# Solar_LEDs.net
KiCad netlist of a schematic drawn in EAGLE
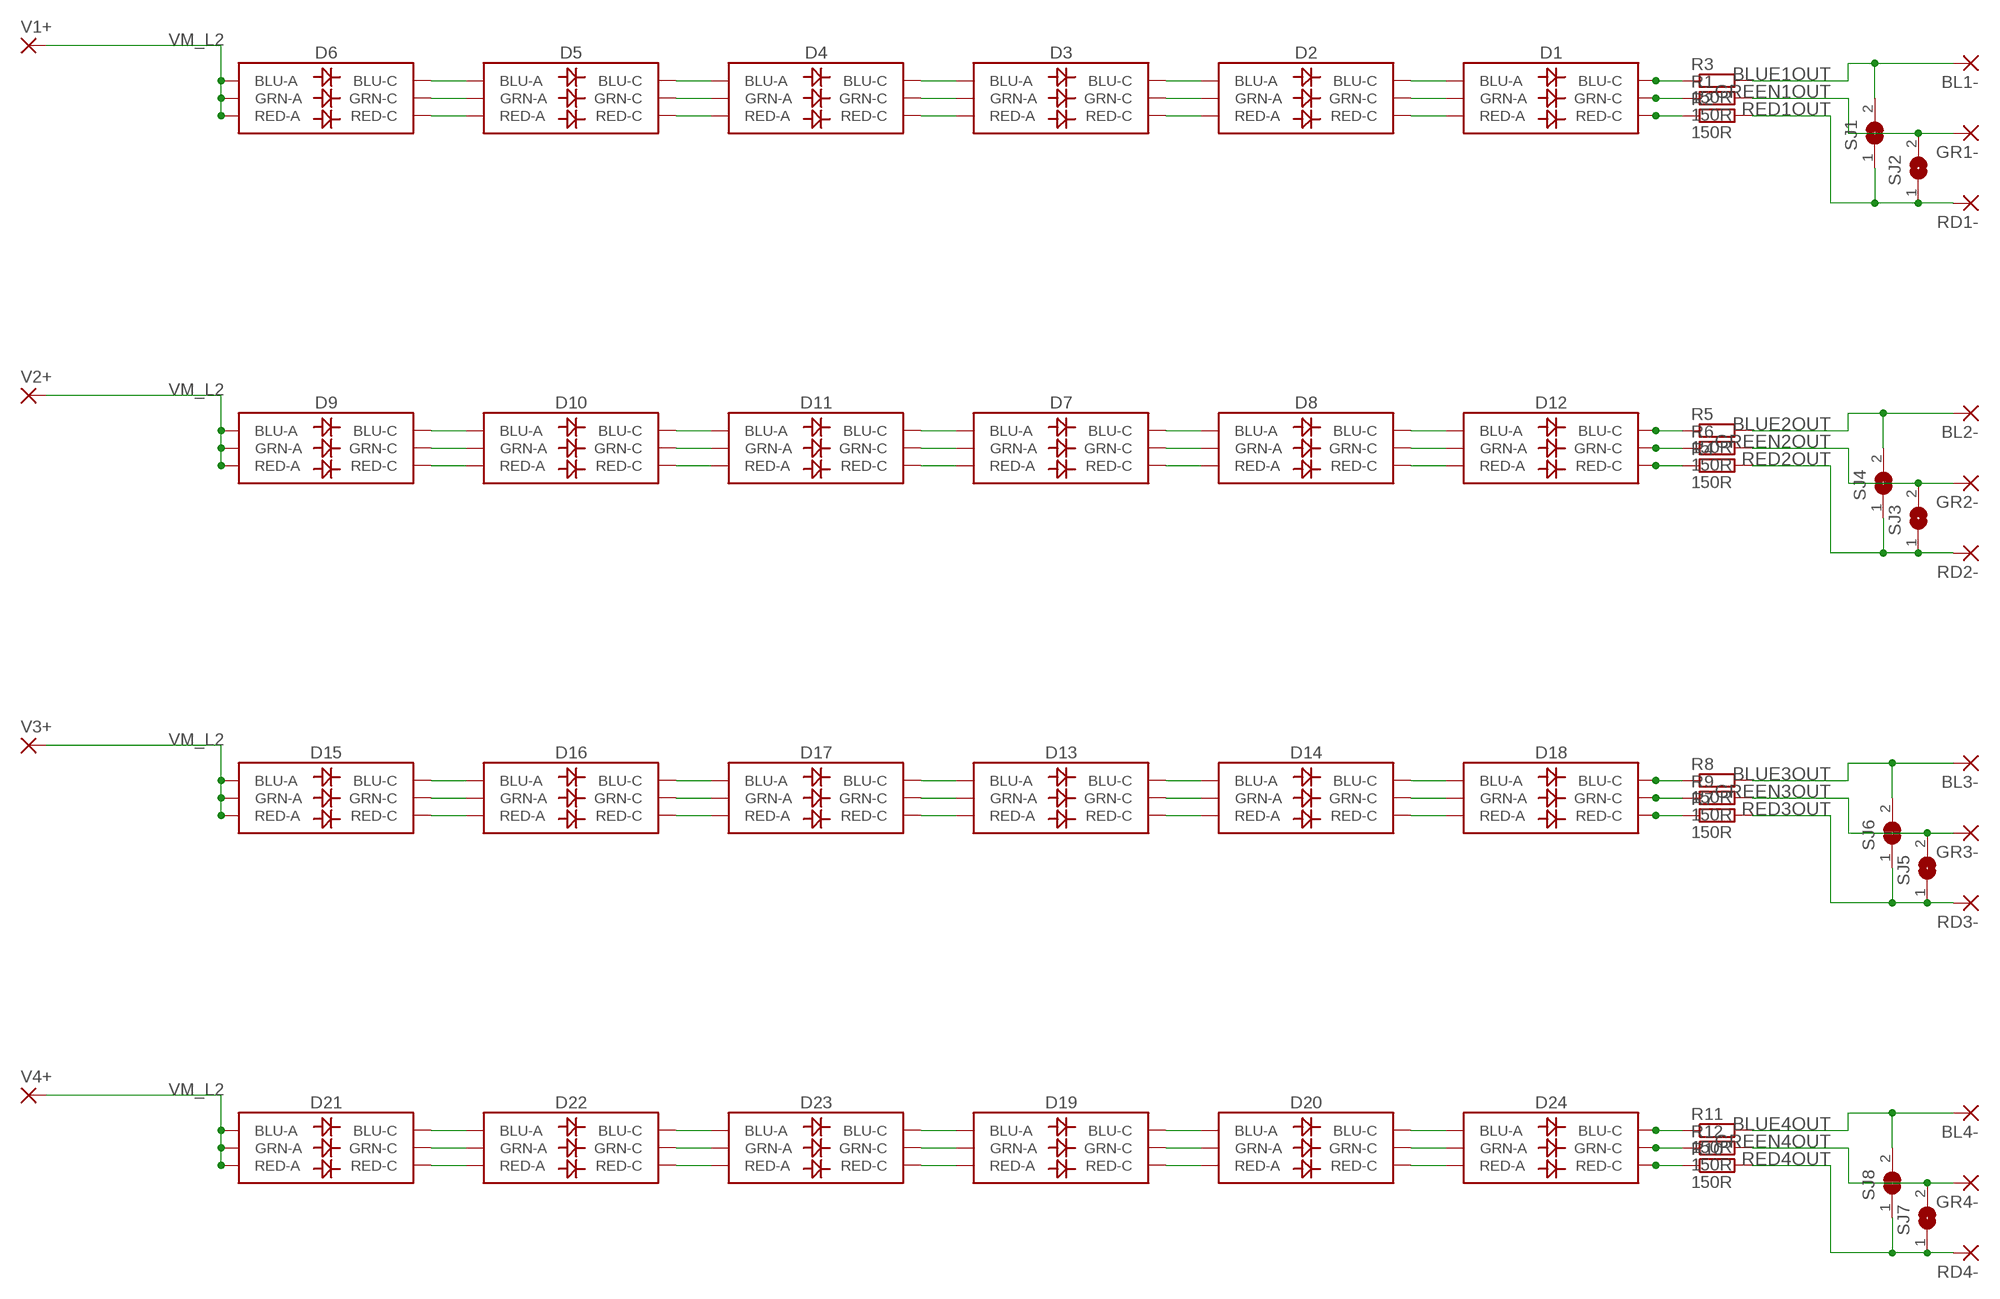
[diagram p0: schematic, sheet 1]

(export (version "E")
  (design (tool "Eeschema 10.0.6"))
  (components
    (comp (ref "BL1-")
      (value "2,54/1,0")
      (footprint "eagle-import:2,54_1,0")
      (libsource (lib "eagle-import") (part "2,54/1,0"))
    )
    (comp (ref "BL2-")
      (value "2,54/1,0")
      (footprint "eagle-import:2,54_1,0")
      (libsource (lib "eagle-import") (part "2,54/1,0"))
    )
    (comp (ref "BL3-")
      (value "2,54/1,0")
      (footprint "eagle-import:2,54_1,0")
      (libsource (lib "eagle-import") (part "2,54/1,0"))
    )
    (comp (ref "BL4-")
      (value "2,54/1,0")
      (footprint "eagle-import:2,54_1,0")
      (libsource (lib "eagle-import") (part "2,54/1,0"))
    )
    (comp (ref "D1")
      (value "LED-RGBNO_IC")
      (footprint "eagle-import:LED-TRICOLOR-5050")
      (libsource (lib "eagle-import") (part "LED-RGBNO_IC"))
    )
    (comp (ref "D2")
      (value "LED-RGBNO_IC")
      (footprint "eagle-import:LED-TRICOLOR-5050")
      (libsource (lib "eagle-import") (part "LED-RGBNO_IC"))
    )
    (comp (ref "D3")
      (value "LED-RGBNO_IC")
      (footprint "eagle-import:LED-TRICOLOR-5050")
      (libsource (lib "eagle-import") (part "LED-RGBNO_IC"))
    )
    (comp (ref "D4")
      (value "LED-RGBNO_IC")
      (footprint "eagle-import:LED-TRICOLOR-5050")
      (libsource (lib "eagle-import") (part "LED-RGBNO_IC"))
    )
    (comp (ref "D5")
      (value "LED-RGBNO_IC")
      (footprint "eagle-import:LED-TRICOLOR-5050")
      (libsource (lib "eagle-import") (part "LED-RGBNO_IC"))
    )
    (comp (ref "D6")
      (value "LED-RGBNO_IC")
      (footprint "eagle-import:LED-TRICOLOR-5050")
      (libsource (lib "eagle-import") (part "LED-RGBNO_IC"))
    )
    (comp (ref "D7")
      (value "LED-RGBNO_IC")
      (footprint "eagle-import:LED-TRICOLOR-5050")
      (libsource (lib "eagle-import") (part "LED-RGBNO_IC"))
    )
    (comp (ref "D8")
      (value "LED-RGBNO_IC")
      (footprint "eagle-import:LED-TRICOLOR-5050")
      (libsource (lib "eagle-import") (part "LED-RGBNO_IC"))
    )
    (comp (ref "D9")
      (value "LED-RGBNO_IC")
      (footprint "eagle-import:LED-TRICOLOR-5050")
      (libsource (lib "eagle-import") (part "LED-RGBNO_IC"))
    )
    (comp (ref "D10")
      (value "LED-RGBNO_IC")
      (footprint "eagle-import:LED-TRICOLOR-5050")
      (libsource (lib "eagle-import") (part "LED-RGBNO_IC"))
    )
    (comp (ref "D11")
      (value "LED-RGBNO_IC")
      (footprint "eagle-import:LED-TRICOLOR-5050")
      (libsource (lib "eagle-import") (part "LED-RGBNO_IC"))
    )
    (comp (ref "D12")
      (value "LED-RGBNO_IC")
      (footprint "eagle-import:LED-TRICOLOR-5050")
      (libsource (lib "eagle-import") (part "LED-RGBNO_IC"))
    )
    (comp (ref "D13")
      (value "LED-RGBNO_IC")
      (footprint "eagle-import:LED-TRICOLOR-5050")
      (libsource (lib "eagle-import") (part "LED-RGBNO_IC"))
    )
    (comp (ref "D14")
      (value "LED-RGBNO_IC")
      (footprint "eagle-import:LED-TRICOLOR-5050")
      (libsource (lib "eagle-import") (part "LED-RGBNO_IC"))
    )
    (comp (ref "D15")
      (value "LED-RGBNO_IC")
      (footprint "eagle-import:LED-TRICOLOR-5050")
      (libsource (lib "eagle-import") (part "LED-RGBNO_IC"))
    )
    (comp (ref "D16")
      (value "LED-RGBNO_IC")
      (footprint "eagle-import:LED-TRICOLOR-5050")
      (libsource (lib "eagle-import") (part "LED-RGBNO_IC"))
    )
    (comp (ref "D17")
      (value "LED-RGBNO_IC")
      (footprint "eagle-import:LED-TRICOLOR-5050")
      (libsource (lib "eagle-import") (part "LED-RGBNO_IC"))
    )
    (comp (ref "D18")
      (value "LED-RGBNO_IC")
      (footprint "eagle-import:LED-TRICOLOR-5050")
      (libsource (lib "eagle-import") (part "LED-RGBNO_IC"))
    )
    (comp (ref "D19")
      (value "LED-RGBNO_IC")
      (footprint "eagle-import:LED-TRICOLOR-5050")
      (libsource (lib "eagle-import") (part "LED-RGBNO_IC"))
    )
    (comp (ref "D20")
      (value "LED-RGBNO_IC")
      (footprint "eagle-import:LED-TRICOLOR-5050")
      (libsource (lib "eagle-import") (part "LED-RGBNO_IC"))
    )
    (comp (ref "D21")
      (value "LED-RGBNO_IC")
      (footprint "eagle-import:LED-TRICOLOR-5050")
      (libsource (lib "eagle-import") (part "LED-RGBNO_IC"))
    )
    (comp (ref "D22")
      (value "LED-RGBNO_IC")
      (footprint "eagle-import:LED-TRICOLOR-5050")
      (libsource (lib "eagle-import") (part "LED-RGBNO_IC"))
    )
    (comp (ref "D23")
      (value "LED-RGBNO_IC")
      (footprint "eagle-import:LED-TRICOLOR-5050")
      (libsource (lib "eagle-import") (part "LED-RGBNO_IC"))
    )
    (comp (ref "D24")
      (value "LED-RGBNO_IC")
      (footprint "eagle-import:LED-TRICOLOR-5050")
      (libsource (lib "eagle-import") (part "LED-RGBNO_IC"))
    )
    (comp (ref "GR1-")
      (value "2,54/1,0")
      (footprint "eagle-import:2,54_1,0")
      (libsource (lib "eagle-import") (part "2,54/1,0"))
    )
    (comp (ref "GR2-")
      (value "2,54/1,0")
      (footprint "eagle-import:2,54_1,0")
      (libsource (lib "eagle-import") (part "2,54/1,0"))
    )
    (comp (ref "GR3-")
      (value "2,54/1,0")
      (footprint "eagle-import:2,54_1,0")
      (libsource (lib "eagle-import") (part "2,54/1,0"))
    )
    (comp (ref "GR4-")
      (value "2,54/1,0")
      (footprint "eagle-import:2,54_1,0")
      (libsource (lib "eagle-import") (part "2,54/1,0"))
    )
    (comp (ref "R1")
      (value "150R")
      (footprint "eagle-import:M1206")
      (libsource (lib "eagle-import") (part "R-EU_M1206"))
    )
    (comp (ref "R2")
      (value "150R")
      (footprint "eagle-import:M1206")
      (libsource (lib "eagle-import") (part "R-EU_M1206"))
    )
    (comp (ref "R3")
      (value "150R")
      (footprint "eagle-import:M1206")
      (libsource (lib "eagle-import") (part "R-EU_M1206"))
    )
    (comp (ref "R4")
      (value "150R")
      (footprint "eagle-import:M1206")
      (libsource (lib "eagle-import") (part "R-EU_M1206"))
    )
    (comp (ref "R5")
      (value "150R")
      (footprint "eagle-import:M1206")
      (libsource (lib "eagle-import") (part "R-EU_M1206"))
    )
    (comp (ref "R6")
      (value "150R")
      (footprint "eagle-import:M1206")
      (libsource (lib "eagle-import") (part "R-EU_M1206"))
    )
    (comp (ref "R7")
      (value "150R")
      (footprint "eagle-import:M1206")
      (libsource (lib "eagle-import") (part "R-EU_M1206"))
    )
    (comp (ref "R8")
      (value "150R")
      (footprint "eagle-import:M1206")
      (libsource (lib "eagle-import") (part "R-EU_M1206"))
    )
    (comp (ref "R9")
      (value "150R")
      (footprint "eagle-import:M1206")
      (libsource (lib "eagle-import") (part "R-EU_M1206"))
    )
    (comp (ref "R10")
      (value "150R")
      (footprint "eagle-import:M1206")
      (libsource (lib "eagle-import") (part "R-EU_M1206"))
    )
    (comp (ref "R11")
      (value "150R")
      (footprint "eagle-import:M1206")
      (libsource (lib "eagle-import") (part "R-EU_M1206"))
    )
    (comp (ref "R12")
      (value "150R")
      (footprint "eagle-import:M1206")
      (libsource (lib "eagle-import") (part "R-EU_M1206"))
    )
    (comp (ref "RD1-")
      (value "2,54/1,0")
      (footprint "eagle-import:2,54_1,0")
      (libsource (lib "eagle-import") (part "2,54/1,0"))
    )
    (comp (ref "RD2-")
      (value "2,54/1,0")
      (footprint "eagle-import:2,54_1,0")
      (libsource (lib "eagle-import") (part "2,54/1,0"))
    )
    (comp (ref "RD3-")
      (value "2,54/1,0")
      (footprint "eagle-import:2,54_1,0")
      (libsource (lib "eagle-import") (part "2,54/1,0"))
    )
    (comp (ref "RD4-")
      (value "2,54/1,0")
      (footprint "eagle-import:2,54_1,0")
      (libsource (lib "eagle-import") (part "2,54/1,0"))
    )
    (comp (ref "SJ1") (value "SJ") (footprint "eagle-import:SJ") (libsource (lib "eagle-import") (part "SJ")))
    (comp (ref "SJ2") (value "SJ") (footprint "eagle-import:SJ") (libsource (lib "eagle-import") (part "SJ")))
    (comp (ref "SJ3") (value "SJ") (footprint "eagle-import:SJ") (libsource (lib "eagle-import") (part "SJ")))
    (comp (ref "SJ4") (value "SJ") (footprint "eagle-import:SJ") (libsource (lib "eagle-import") (part "SJ")))
    (comp (ref "SJ5") (value "SJ") (footprint "eagle-import:SJ") (libsource (lib "eagle-import") (part "SJ")))
    (comp (ref "SJ6") (value "SJ") (footprint "eagle-import:SJ") (libsource (lib "eagle-import") (part "SJ")))
    (comp (ref "SJ7") (value "SJ") (footprint "eagle-import:SJ") (libsource (lib "eagle-import") (part "SJ")))
    (comp (ref "SJ8") (value "SJ") (footprint "eagle-import:SJ") (libsource (lib "eagle-import") (part "SJ")))
    (comp (ref "V1+")
      (value "2,54/1,0")
      (footprint "eagle-import:2,54_1,0")
      (libsource (lib "eagle-import") (part "2,54/1,0"))
    )
    (comp (ref "V2+")
      (value "2,54/1,0")
      (footprint "eagle-import:2,54_1,0")
      (libsource (lib "eagle-import") (part "2,54/1,0"))
    )
    (comp (ref "V3+")
      (value "2,54/1,0")
      (footprint "eagle-import:2,54_1,0")
      (libsource (lib "eagle-import") (part "2,54/1,0"))
    )
    (comp (ref "V4+")
      (value "2,54/1,0")
      (footprint "eagle-import:2,54_1,0")
      (libsource (lib "eagle-import") (part "2,54/1,0"))
    )
  )
  (nets
    (net (code "1") (name "/BLUE1OUT") (class "Default")
      (node (ref "BL1-") (pin "1") (pinfunction "P_1") (pintype "passive"))
      (node (ref "R3") (pin "2") (pinfunction "2_2") (pintype "passive"))
      (node (ref "SJ1") (pin "2") (pinfunction "2_2") (pintype "passive"))
    )
    (net (code "2") (name "/BLUE2OUT") (class "Default")
      (node (ref "BL2-") (pin "1") (pinfunction "P_1") (pintype "passive"))
      (node (ref "R5") (pin "2") (pinfunction "2_2") (pintype "passive"))
      (node (ref "SJ4") (pin "2") (pinfunction "2_2") (pintype "passive"))
    )
    (net (code "3") (name "/BLUE3OUT") (class "Default")
      (node (ref "BL3-") (pin "1") (pinfunction "P_1") (pintype "passive"))
      (node (ref "R8") (pin "2") (pinfunction "2_2") (pintype "passive"))
      (node (ref "SJ6") (pin "2") (pinfunction "2_2") (pintype "passive"))
    )
    (net (code "4") (name "/BLUE4OUT") (class "Default")
      (node (ref "BL4-") (pin "1") (pinfunction "P_1") (pintype "passive"))
      (node (ref "R11") (pin "2") (pinfunction "2_2") (pintype "passive"))
      (node (ref "SJ8") (pin "2") (pinfunction "2_2") (pintype "passive"))
    )
    (net (code "5") (name "/GREEN1OUT") (class "Default")
      (node (ref "GR1-") (pin "1") (pinfunction "P_1") (pintype "passive"))
      (node (ref "R1") (pin "2") (pinfunction "2_2") (pintype "passive"))
      (node (ref "SJ2") (pin "2") (pinfunction "2_2") (pintype "passive"))
    )
    (net (code "6") (name "/GREEN2OUT") (class "Default")
      (node (ref "GR2-") (pin "1") (pinfunction "P_1") (pintype "passive"))
      (node (ref "R6") (pin "2") (pinfunction "2_2") (pintype "passive"))
      (node (ref "SJ3") (pin "2") (pinfunction "2_2") (pintype "passive"))
    )
    (net (code "7") (name "/GREEN3OUT") (class "Default")
      (node (ref "GR3-") (pin "1") (pinfunction "P_1") (pintype "passive"))
      (node (ref "R9") (pin "2") (pinfunction "2_2") (pintype "passive"))
      (node (ref "SJ5") (pin "2") (pinfunction "2_2") (pintype "passive"))
    )
    (net (code "8") (name "/GREEN4OUT") (class "Default")
      (node (ref "GR4-") (pin "1") (pinfunction "P_1") (pintype "passive"))
      (node (ref "R12") (pin "2") (pinfunction "2_2") (pintype "passive"))
      (node (ref "SJ7") (pin "2") (pinfunction "2_2") (pintype "passive"))
    )
    (net (code "9") (name "/RED1OUT") (class "Default")
      (node (ref "R2") (pin "2") (pinfunction "2_2") (pintype "passive"))
      (node (ref "RD1-") (pin "1") (pinfunction "P_1") (pintype "passive"))
      (node (ref "SJ1") (pin "1") (pinfunction "1_1") (pintype "passive"))
      (node (ref "SJ2") (pin "1") (pinfunction "1_1") (pintype "passive"))
    )
    (net (code "10") (name "/RED2OUT") (class "Default")
      (node (ref "R4") (pin "2") (pinfunction "2_2") (pintype "passive"))
      (node (ref "RD2-") (pin "1") (pinfunction "P_1") (pintype "passive"))
      (node (ref "SJ3") (pin "1") (pinfunction "1_1") (pintype "passive"))
      (node (ref "SJ4") (pin "1") (pinfunction "1_1") (pintype "passive"))
    )
    (net (code "11") (name "/RED3OUT") (class "Default")
      (node (ref "R7") (pin "2") (pinfunction "2_2") (pintype "passive"))
      (node (ref "RD3-") (pin "1") (pinfunction "P_1") (pintype "passive"))
      (node (ref "SJ5") (pin "1") (pinfunction "1_1") (pintype "passive"))
      (node (ref "SJ6") (pin "1") (pinfunction "1_1") (pintype "passive"))
    )
    (net (code "12") (name "/RED4OUT") (class "Default")
      (node (ref "R10") (pin "2") (pinfunction "2_2") (pintype "passive"))
      (node (ref "RD4-") (pin "1") (pinfunction "P_1") (pintype "passive"))
      (node (ref "SJ7") (pin "1") (pinfunction "1_1") (pintype "passive"))
      (node (ref "SJ8") (pin "1") (pinfunction "1_1") (pintype "passive"))
    )
    (net (code "13") (name "/VM_L2") (class "Default")
      (node (ref "D15") (pin "1") (pinfunction "GRN-A_1") (pintype "bidirectional"))
      (node (ref "D15") (pin "2") (pinfunction "RED-A_2") (pintype "bidirectional"))
      (node (ref "D15") (pin "3") (pinfunction "BLU-A_3") (pintype "bidirectional"))
      (node (ref "D21") (pin "1") (pinfunction "GRN-A_1") (pintype "bidirectional"))
      (node (ref "D21") (pin "2") (pinfunction "RED-A_2") (pintype "bidirectional"))
      (node (ref "D21") (pin "3") (pinfunction "BLU-A_3") (pintype "bidirectional"))
      (node (ref "D6") (pin "1") (pinfunction "GRN-A_1") (pintype "bidirectional"))
      (node (ref "D6") (pin "2") (pinfunction "RED-A_2") (pintype "bidirectional"))
      (node (ref "D6") (pin "3") (pinfunction "BLU-A_3") (pintype "bidirectional"))
      (node (ref "D9") (pin "1") (pinfunction "GRN-A_1") (pintype "bidirectional"))
      (node (ref "D9") (pin "2") (pinfunction "RED-A_2") (pintype "bidirectional"))
      (node (ref "D9") (pin "3") (pinfunction "BLU-A_3") (pintype "bidirectional"))
      (node (ref "V1+") (pin "1") (pinfunction "P_1") (pintype "passive"))
      (node (ref "V2+") (pin "1") (pinfunction "P_1") (pintype "passive"))
      (node (ref "V3+") (pin "1") (pinfunction "P_1") (pintype "passive"))
      (node (ref "V4+") (pin "1") (pinfunction "P_1") (pintype "passive"))
    )
    (net (code "14") (name "Net-(D1-BLU-A)") (class "Default")
      (node (ref "D1") (pin "3") (pinfunction "BLU-A_3") (pintype "bidirectional"))
      (node (ref "D2") (pin "4") (pinfunction "BLU-C_4") (pintype "bidirectional"))
    )
    (net (code "15") (name "Net-(D1-BLU-C)") (class "Default")
      (node (ref "D1") (pin "4") (pinfunction "BLU-C_4") (pintype "bidirectional"))
      (node (ref "R3") (pin "1") (pinfunction "1_1") (pintype "passive"))
    )
    (net (code "16") (name "Net-(D1-GRN-A)") (class "Default")
      (node (ref "D1") (pin "1") (pinfunction "GRN-A_1") (pintype "bidirectional"))
      (node (ref "D2") (pin "6") (pinfunction "GRN-C_6") (pintype "bidirectional"))
    )
    (net (code "17") (name "Net-(D1-GRN-C)") (class "Default")
      (node (ref "D1") (pin "6") (pinfunction "GRN-C_6") (pintype "bidirectional"))
      (node (ref "R1") (pin "1") (pinfunction "1_1") (pintype "passive"))
    )
    (net (code "18") (name "Net-(D1-RED-A)") (class "Default")
      (node (ref "D1") (pin "2") (pinfunction "RED-A_2") (pintype "bidirectional"))
      (node (ref "D2") (pin "5") (pinfunction "RED-C_5") (pintype "bidirectional"))
    )
    (net (code "19") (name "Net-(D1-RED-C)") (class "Default")
      (node (ref "D1") (pin "5") (pinfunction "RED-C_5") (pintype "bidirectional"))
      (node (ref "R2") (pin "1") (pinfunction "1_1") (pintype "passive"))
    )
    (net (code "20") (name "Net-(D2-BLU-A)") (class "Default")
      (node (ref "D2") (pin "3") (pinfunction "BLU-A_3") (pintype "bidirectional"))
      (node (ref "D3") (pin "4") (pinfunction "BLU-C_4") (pintype "bidirectional"))
    )
    (net (code "21") (name "Net-(D2-GRN-A)") (class "Default")
      (node (ref "D2") (pin "1") (pinfunction "GRN-A_1") (pintype "bidirectional"))
      (node (ref "D3") (pin "6") (pinfunction "GRN-C_6") (pintype "bidirectional"))
    )
    (net (code "22") (name "Net-(D2-RED-A)") (class "Default")
      (node (ref "D2") (pin "2") (pinfunction "RED-A_2") (pintype "bidirectional"))
      (node (ref "D3") (pin "5") (pinfunction "RED-C_5") (pintype "bidirectional"))
    )
    (net (code "23") (name "Net-(D3-BLU-A)") (class "Default")
      (node (ref "D3") (pin "3") (pinfunction "BLU-A_3") (pintype "bidirectional"))
      (node (ref "D4") (pin "4") (pinfunction "BLU-C_4") (pintype "bidirectional"))
    )
    (net (code "24") (name "Net-(D3-GRN-A)") (class "Default")
      (node (ref "D3") (pin "1") (pinfunction "GRN-A_1") (pintype "bidirectional"))
      (node (ref "D4") (pin "6") (pinfunction "GRN-C_6") (pintype "bidirectional"))
    )
    (net (code "25") (name "Net-(D3-RED-A)") (class "Default")
      (node (ref "D3") (pin "2") (pinfunction "RED-A_2") (pintype "bidirectional"))
      (node (ref "D4") (pin "5") (pinfunction "RED-C_5") (pintype "bidirectional"))
    )
    (net (code "26") (name "Net-(D4-BLU-A)") (class "Default")
      (node (ref "D4") (pin "3") (pinfunction "BLU-A_3") (pintype "bidirectional"))
      (node (ref "D5") (pin "4") (pinfunction "BLU-C_4") (pintype "bidirectional"))
    )
    (net (code "27") (name "Net-(D4-GRN-A)") (class "Default")
      (node (ref "D4") (pin "1") (pinfunction "GRN-A_1") (pintype "bidirectional"))
      (node (ref "D5") (pin "6") (pinfunction "GRN-C_6") (pintype "bidirectional"))
    )
    (net (code "28") (name "Net-(D4-RED-A)") (class "Default")
      (node (ref "D4") (pin "2") (pinfunction "RED-A_2") (pintype "bidirectional"))
      (node (ref "D5") (pin "5") (pinfunction "RED-C_5") (pintype "bidirectional"))
    )
    (net (code "29") (name "Net-(D5-BLU-A)") (class "Default")
      (node (ref "D5") (pin "3") (pinfunction "BLU-A_3") (pintype "bidirectional"))
      (node (ref "D6") (pin "4") (pinfunction "BLU-C_4") (pintype "bidirectional"))
    )
    (net (code "30") (name "Net-(D5-GRN-A)") (class "Default")
      (node (ref "D5") (pin "1") (pinfunction "GRN-A_1") (pintype "bidirectional"))
      (node (ref "D6") (pin "6") (pinfunction "GRN-C_6") (pintype "bidirectional"))
    )
    (net (code "31") (name "Net-(D5-RED-A)") (class "Default")
      (node (ref "D5") (pin "2") (pinfunction "RED-A_2") (pintype "bidirectional"))
      (node (ref "D6") (pin "5") (pinfunction "RED-C_5") (pintype "bidirectional"))
    )
    (net (code "32") (name "Net-(D7-BLU-C)") (class "Default")
      (node (ref "D7") (pin "4") (pinfunction "BLU-C_4") (pintype "bidirectional"))
      (node (ref "D8") (pin "3") (pinfunction "BLU-A_3") (pintype "bidirectional"))
    )
    (net (code "33") (name "Net-(D7-GRN-C)") (class "Default")
      (node (ref "D7") (pin "6") (pinfunction "GRN-C_6") (pintype "bidirectional"))
      (node (ref "D8") (pin "1") (pinfunction "GRN-A_1") (pintype "bidirectional"))
    )
    (net (code "34") (name "Net-(D7-RED-C)") (class "Default")
      (node (ref "D7") (pin "5") (pinfunction "RED-C_5") (pintype "bidirectional"))
      (node (ref "D8") (pin "2") (pinfunction "RED-A_2") (pintype "bidirectional"))
    )
    (net (code "35") (name "Net-(D10-BLU-A)") (class "Default")
      (node (ref "D10") (pin "3") (pinfunction "BLU-A_3") (pintype "bidirectional"))
      (node (ref "D9") (pin "4") (pinfunction "BLU-C_4") (pintype "bidirectional"))
    )
    (net (code "36") (name "Net-(D10-BLU-C)") (class "Default")
      (node (ref "D10") (pin "4") (pinfunction "BLU-C_4") (pintype "bidirectional"))
      (node (ref "D11") (pin "3") (pinfunction "BLU-A_3") (pintype "bidirectional"))
    )
    (net (code "37") (name "Net-(D10-GRN-A)") (class "Default")
      (node (ref "D10") (pin "1") (pinfunction "GRN-A_1") (pintype "bidirectional"))
      (node (ref "D9") (pin "6") (pinfunction "GRN-C_6") (pintype "bidirectional"))
    )
    (net (code "38") (name "Net-(D10-GRN-C)") (class "Default")
      (node (ref "D10") (pin "6") (pinfunction "GRN-C_6") (pintype "bidirectional"))
      (node (ref "D11") (pin "1") (pinfunction "GRN-A_1") (pintype "bidirectional"))
    )
    (net (code "39") (name "Net-(D10-RED-A)") (class "Default")
      (node (ref "D10") (pin "2") (pinfunction "RED-A_2") (pintype "bidirectional"))
      (node (ref "D9") (pin "5") (pinfunction "RED-C_5") (pintype "bidirectional"))
    )
    (net (code "40") (name "Net-(D10-RED-C)") (class "Default")
      (node (ref "D10") (pin "5") (pinfunction "RED-C_5") (pintype "bidirectional"))
      (node (ref "D11") (pin "2") (pinfunction "RED-A_2") (pintype "bidirectional"))
    )
    (net (code "41") (name "Net-(D11-BLU-C)") (class "Default")
      (node (ref "D11") (pin "4") (pinfunction "BLU-C_4") (pintype "bidirectional"))
      (node (ref "D7") (pin "3") (pinfunction "BLU-A_3") (pintype "bidirectional"))
    )
    (net (code "42") (name "Net-(D11-GRN-C)") (class "Default")
      (node (ref "D11") (pin "6") (pinfunction "GRN-C_6") (pintype "bidirectional"))
      (node (ref "D7") (pin "1") (pinfunction "GRN-A_1") (pintype "bidirectional"))
    )
    (net (code "43") (name "Net-(D11-RED-C)") (class "Default")
      (node (ref "D11") (pin "5") (pinfunction "RED-C_5") (pintype "bidirectional"))
      (node (ref "D7") (pin "2") (pinfunction "RED-A_2") (pintype "bidirectional"))
    )
    (net (code "44") (name "Net-(D12-BLU-A)") (class "Default")
      (node (ref "D12") (pin "3") (pinfunction "BLU-A_3") (pintype "bidirectional"))
      (node (ref "D8") (pin "4") (pinfunction "BLU-C_4") (pintype "bidirectional"))
    )
    (net (code "45") (name "Net-(D12-BLU-C)") (class "Default")
      (node (ref "D12") (pin "4") (pinfunction "BLU-C_4") (pintype "bidirectional"))
      (node (ref "R5") (pin "1") (pinfunction "1_1") (pintype "passive"))
    )
    (net (code "46") (name "Net-(D12-GRN-A)") (class "Default")
      (node (ref "D12") (pin "1") (pinfunction "GRN-A_1") (pintype "bidirectional"))
      (node (ref "D8") (pin "6") (pinfunction "GRN-C_6") (pintype "bidirectional"))
    )
    (net (code "47") (name "Net-(D12-GRN-C)") (class "Default")
      (node (ref "D12") (pin "6") (pinfunction "GRN-C_6") (pintype "bidirectional"))
      (node (ref "R6") (pin "1") (pinfunction "1_1") (pintype "passive"))
    )
    (net (code "48") (name "Net-(D12-RED-A)") (class "Default")
      (node (ref "D12") (pin "2") (pinfunction "RED-A_2") (pintype "bidirectional"))
      (node (ref "D8") (pin "5") (pinfunction "RED-C_5") (pintype "bidirectional"))
    )
    (net (code "49") (name "Net-(D12-RED-C)") (class "Default")
      (node (ref "D12") (pin "5") (pinfunction "RED-C_5") (pintype "bidirectional"))
      (node (ref "R4") (pin "1") (pinfunction "1_1") (pintype "passive"))
    )
    (net (code "50") (name "Net-(D13-BLU-A)") (class "Default")
      (node (ref "D13") (pin "3") (pinfunction "BLU-A_3") (pintype "bidirectional"))
      (node (ref "D17") (pin "4") (pinfunction "BLU-C_4") (pintype "bidirectional"))
    )
    (net (code "51") (name "Net-(D13-BLU-C)") (class "Default")
      (node (ref "D13") (pin "4") (pinfunction "BLU-C_4") (pintype "bidirectional"))
      (node (ref "D14") (pin "3") (pinfunction "BLU-A_3") (pintype "bidirectional"))
    )
    (net (code "52") (name "Net-(D13-GRN-A)") (class "Default")
      (node (ref "D13") (pin "1") (pinfunction "GRN-A_1") (pintype "bidirectional"))
      (node (ref "D17") (pin "6") (pinfunction "GRN-C_6") (pintype "bidirectional"))
    )
    (net (code "53") (name "Net-(D13-GRN-C)") (class "Default")
      (node (ref "D13") (pin "6") (pinfunction "GRN-C_6") (pintype "bidirectional"))
      (node (ref "D14") (pin "1") (pinfunction "GRN-A_1") (pintype "bidirectional"))
    )
    (net (code "54") (name "Net-(D13-RED-A)") (class "Default")
      (node (ref "D13") (pin "2") (pinfunction "RED-A_2") (pintype "bidirectional"))
      (node (ref "D17") (pin "5") (pinfunction "RED-C_5") (pintype "bidirectional"))
    )
    (net (code "55") (name "Net-(D13-RED-C)") (class "Default")
      (node (ref "D13") (pin "5") (pinfunction "RED-C_5") (pintype "bidirectional"))
      (node (ref "D14") (pin "2") (pinfunction "RED-A_2") (pintype "bidirectional"))
    )
    (net (code "56") (name "Net-(D14-BLU-C)") (class "Default")
      (node (ref "D14") (pin "4") (pinfunction "BLU-C_4") (pintype "bidirectional"))
      (node (ref "D18") (pin "3") (pinfunction "BLU-A_3") (pintype "bidirectional"))
    )
    (net (code "57") (name "Net-(D14-GRN-C)") (class "Default")
      (node (ref "D14") (pin "6") (pinfunction "GRN-C_6") (pintype "bidirectional"))
      (node (ref "D18") (pin "1") (pinfunction "GRN-A_1") (pintype "bidirectional"))
    )
    (net (code "58") (name "Net-(D14-RED-C)") (class "Default")
      (node (ref "D14") (pin "5") (pinfunction "RED-C_5") (pintype "bidirectional"))
      (node (ref "D18") (pin "2") (pinfunction "RED-A_2") (pintype "bidirectional"))
    )
    (net (code "59") (name "Net-(D15-BLU-C)") (class "Default")
      (node (ref "D15") (pin "4") (pinfunction "BLU-C_4") (pintype "bidirectional"))
      (node (ref "D16") (pin "3") (pinfunction "BLU-A_3") (pintype "bidirectional"))
    )
    (net (code "60") (name "Net-(D15-GRN-C)") (class "Default")
      (node (ref "D15") (pin "6") (pinfunction "GRN-C_6") (pintype "bidirectional"))
      (node (ref "D16") (pin "1") (pinfunction "GRN-A_1") (pintype "bidirectional"))
    )
    (net (code "61") (name "Net-(D15-RED-C)") (class "Default")
      (node (ref "D15") (pin "5") (pinfunction "RED-C_5") (pintype "bidirectional"))
      (node (ref "D16") (pin "2") (pinfunction "RED-A_2") (pintype "bidirectional"))
    )
    (net (code "62") (name "Net-(D16-BLU-C)") (class "Default")
      (node (ref "D16") (pin "4") (pinfunction "BLU-C_4") (pintype "bidirectional"))
      (node (ref "D17") (pin "3") (pinfunction "BLU-A_3") (pintype "bidirectional"))
    )
    (net (code "63") (name "Net-(D16-GRN-C)") (class "Default")
      (node (ref "D16") (pin "6") (pinfunction "GRN-C_6") (pintype "bidirectional"))
      (node (ref "D17") (pin "1") (pinfunction "GRN-A_1") (pintype "bidirectional"))
    )
    (net (code "64") (name "Net-(D16-RED-C)") (class "Default")
      (node (ref "D16") (pin "5") (pinfunction "RED-C_5") (pintype "bidirectional"))
      (node (ref "D17") (pin "2") (pinfunction "RED-A_2") (pintype "bidirectional"))
    )
    (net (code "65") (name "Net-(D18-BLU-C)") (class "Default")
      (node (ref "D18") (pin "4") (pinfunction "BLU-C_4") (pintype "bidirectional"))
      (node (ref "R8") (pin "1") (pinfunction "1_1") (pintype "passive"))
    )
    (net (code "66") (name "Net-(D18-GRN-C)") (class "Default")
      (node (ref "D18") (pin "6") (pinfunction "GRN-C_6") (pintype "bidirectional"))
      (node (ref "R9") (pin "1") (pinfunction "1_1") (pintype "passive"))
    )
    (net (code "67") (name "Net-(D18-RED-C)") (class "Default")
      (node (ref "D18") (pin "5") (pinfunction "RED-C_5") (pintype "bidirectional"))
      (node (ref "R7") (pin "1") (pinfunction "1_1") (pintype "passive"))
    )
    (net (code "68") (name "Net-(D19-BLU-A)") (class "Default")
      (node (ref "D19") (pin "3") (pinfunction "BLU-A_3") (pintype "bidirectional"))
      (node (ref "D23") (pin "4") (pinfunction "BLU-C_4") (pintype "bidirectional"))
    )
    (net (code "69") (name "Net-(D19-BLU-C)") (class "Default")
      (node (ref "D19") (pin "4") (pinfunction "BLU-C_4") (pintype "bidirectional"))
      (node (ref "D20") (pin "3") (pinfunction "BLU-A_3") (pintype "bidirectional"))
    )
    (net (code "70") (name "Net-(D19-GRN-A)") (class "Default")
      (node (ref "D19") (pin "1") (pinfunction "GRN-A_1") (pintype "bidirectional"))
      (node (ref "D23") (pin "6") (pinfunction "GRN-C_6") (pintype "bidirectional"))
    )
    (net (code "71") (name "Net-(D19-GRN-C)") (class "Default")
      (node (ref "D19") (pin "6") (pinfunction "GRN-C_6") (pintype "bidirectional"))
      (node (ref "D20") (pin "1") (pinfunction "GRN-A_1") (pintype "bidirectional"))
    )
    (net (code "72") (name "Net-(D19-RED-A)") (class "Default")
      (node (ref "D19") (pin "2") (pinfunction "RED-A_2") (pintype "bidirectional"))
      (node (ref "D23") (pin "5") (pinfunction "RED-C_5") (pintype "bidirectional"))
    )
    (net (code "73") (name "Net-(D19-RED-C)") (class "Default")
      (node (ref "D19") (pin "5") (pinfunction "RED-C_5") (pintype "bidirectional"))
      (node (ref "D20") (pin "2") (pinfunction "RED-A_2") (pintype "bidirectional"))
    )
    (net (code "74") (name "Net-(D20-BLU-C)") (class "Default")
      (node (ref "D20") (pin "4") (pinfunction "BLU-C_4") (pintype "bidirectional"))
      (node (ref "D24") (pin "3") (pinfunction "BLU-A_3") (pintype "bidirectional"))
    )
    (net (code "75") (name "Net-(D20-GRN-C)") (class "Default")
      (node (ref "D20") (pin "6") (pinfunction "GRN-C_6") (pintype "bidirectional"))
      (node (ref "D24") (pin "1") (pinfunction "GRN-A_1") (pintype "bidirectional"))
    )
    (net (code "76") (name "Net-(D20-RED-C)") (class "Default")
      (node (ref "D20") (pin "5") (pinfunction "RED-C_5") (pintype "bidirectional"))
      (node (ref "D24") (pin "2") (pinfunction "RED-A_2") (pintype "bidirectional"))
    )
    (net (code "77") (name "Net-(D21-BLU-C)") (class "Default")
      (node (ref "D21") (pin "4") (pinfunction "BLU-C_4") (pintype "bidirectional"))
      (node (ref "D22") (pin "3") (pinfunction "BLU-A_3") (pintype "bidirectional"))
    )
    (net (code "78") (name "Net-(D21-GRN-C)") (class "Default")
      (node (ref "D21") (pin "6") (pinfunction "GRN-C_6") (pintype "bidirectional"))
      (node (ref "D22") (pin "1") (pinfunction "GRN-A_1") (pintype "bidirectional"))
    )
    (net (code "79") (name "Net-(D21-RED-C)") (class "Default")
      (node (ref "D21") (pin "5") (pinfunction "RED-C_5") (pintype "bidirectional"))
      (node (ref "D22") (pin "2") (pinfunction "RED-A_2") (pintype "bidirectional"))
    )
    (net (code "80") (name "Net-(D22-BLU-C)") (class "Default")
      (node (ref "D22") (pin "4") (pinfunction "BLU-C_4") (pintype "bidirectional"))
      (node (ref "D23") (pin "3") (pinfunction "BLU-A_3") (pintype "bidirectional"))
    )
    (net (code "81") (name "Net-(D22-GRN-C)") (class "Default")
      (node (ref "D22") (pin "6") (pinfunction "GRN-C_6") (pintype "bidirectional"))
      (node (ref "D23") (pin "1") (pinfunction "GRN-A_1") (pintype "bidirectional"))
    )
    (net (code "82") (name "Net-(D22-RED-C)") (class "Default")
      (node (ref "D22") (pin "5") (pinfunction "RED-C_5") (pintype "bidirectional"))
      (node (ref "D23") (pin "2") (pinfunction "RED-A_2") (pintype "bidirectional"))
    )
    (net (code "83") (name "Net-(D24-BLU-C)") (class "Default")
      (node (ref "D24") (pin "4") (pinfunction "BLU-C_4") (pintype "bidirectional"))
      (node (ref "R11") (pin "1") (pinfunction "1_1") (pintype "passive"))
    )
    (net (code "84") (name "Net-(D24-GRN-C)") (class "Default")
      (node (ref "D24") (pin "6") (pinfunction "GRN-C_6") (pintype "bidirectional"))
      (node (ref "R12") (pin "1") (pinfunction "1_1") (pintype "passive"))
    )
    (net (code "85") (name "Net-(D24-RED-C)") (class "Default")
      (node (ref "D24") (pin "5") (pinfunction "RED-C_5") (pintype "bidirectional"))
      (node (ref "R10") (pin "1") (pinfunction "1_1") (pintype "passive"))
    )
  )
)
